# SP.net
KiCad netlist of a schematic drawn in EAGLE
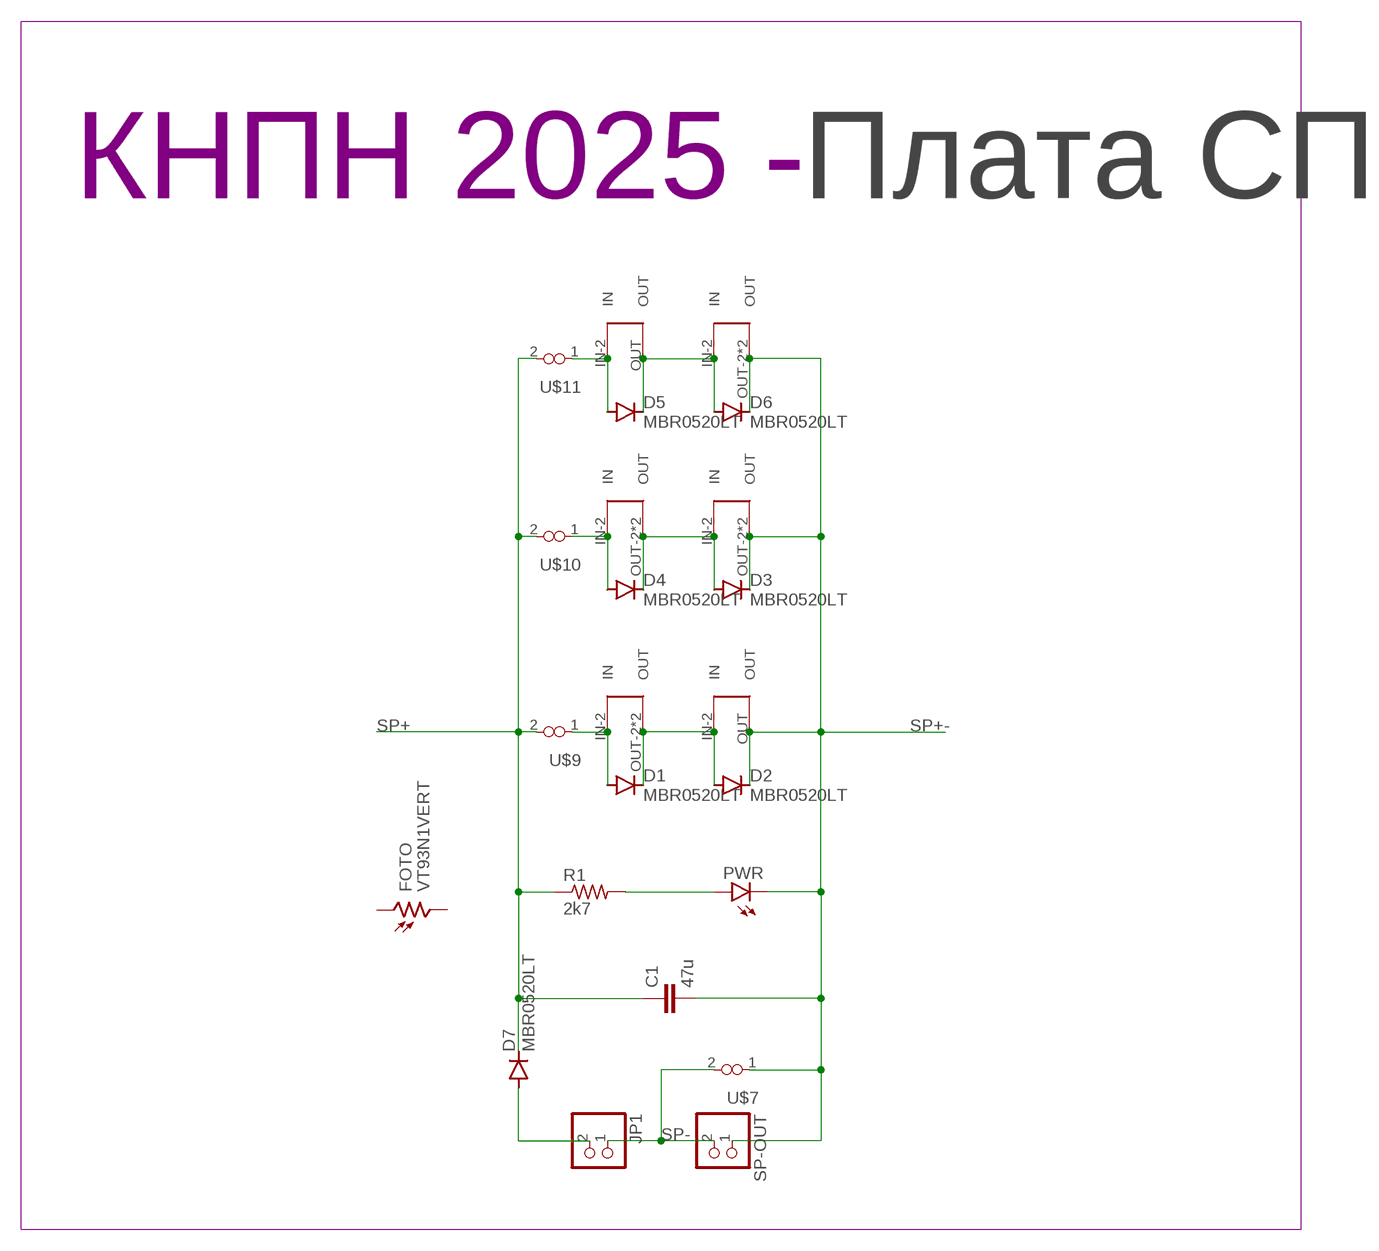
[diagram p0: schematic, sheet 1]

(export (version "E")
  (design (tool "Eeschema 10.0.6"))
  (components
    (comp (ref "C1")
      (value "47u")
      (footprint "eagle-import:C1210")
      (libsource (lib "eagle-import") (part "C-EUC1210"))
    )
    (comp (ref "D1")
      (value "MBR0520LT")
      (footprint "eagle-import:SOD123")
      (libsource (lib "eagle-import") (part "MBR0520LT"))
    )
    (comp (ref "D2")
      (value "MBR0520LT")
      (footprint "eagle-import:SOD123")
      (libsource (lib "eagle-import") (part "MBR0520LT"))
    )
    (comp (ref "D3")
      (value "MBR0520LT")
      (footprint "eagle-import:SOD123")
      (libsource (lib "eagle-import") (part "MBR0520LT"))
    )
    (comp (ref "D4")
      (value "MBR0520LT")
      (footprint "eagle-import:SOD123")
      (libsource (lib "eagle-import") (part "MBR0520LT"))
    )
    (comp (ref "D5")
      (value "MBR0520LT")
      (footprint "eagle-import:SOD123")
      (libsource (lib "eagle-import") (part "MBR0520LT"))
    )
    (comp (ref "D6")
      (value "MBR0520LT")
      (footprint "eagle-import:SOD123")
      (libsource (lib "eagle-import") (part "MBR0520LT"))
    )
    (comp (ref "D7")
      (value "MBR0520LT")
      (footprint "eagle-import:SOD123")
      (libsource (lib "eagle-import") (part "MBR0520LT"))
    )
    (comp (ref "FOTO")
      (value "VT93N1VERT")
      (footprint "eagle-import:VT93N1-VERT")
      (libsource (lib "eagle-import") (part "VT93N1VERT"))
    )
    (comp (ref "JP1")
      (value "PINHD-1X2")
      (footprint "eagle-import:1X02")
      (libsource (lib "eagle-import") (part "PINHD-1X2"))
    )
    (comp (ref "PWR")
      (value "LEDCHIP-LED0603")
      (footprint "eagle-import:CHIP-LED0603")
      (libsource (lib "eagle-import") (part "LEDCHIP-LED0603"))
    )
    (comp (ref "R1")
      (value "2k7")
      (footprint "eagle-import:R0603")
      (libsource (lib "eagle-import") (part "R-US_R0603"))
    )
    (comp (ref "SP-OUT")
      (value "PINHD-1X2")
      (footprint "eagle-import:1X02")
      (libsource (lib "eagle-import") (part "PINHD-1X2"))
    )
    (comp (ref "U$1")
      (value "SOLAR-2_INVERT0-2")
      (footprint "eagle-import:SOLAR_0-2_INVERT")
      (libsource (lib "eagle-import") (part "SOLAR-2_INVERT0-2"))
    )
    (comp (ref "U$2")
      (value "SOLAR-2_INVERT1-2")
      (footprint "eagle-import:SOLAR_1-2_INVERT")
      (libsource (lib "eagle-import") (part "SOLAR-2_INVERT1-2"))
    )
    (comp (ref "U$3")
      (value "SOLAR-2_INVERT0-2")
      (footprint "eagle-import:SOLAR_0-2_INVERT")
      (libsource (lib "eagle-import") (part "SOLAR-2_INVERT0-2"))
    )
    (comp (ref "U$4")
      (value "SOLAR-2_INVERT0-2")
      (footprint "eagle-import:SOLAR_0-2_INVERT")
      (libsource (lib "eagle-import") (part "SOLAR-2_INVERT0-2"))
    )
    (comp (ref "U$5")
      (value "Плата СП")
      (footprint "eagle-import:LOGO")
      (libsource (lib "eagle-import") (part "LOGOPCB-{dblquote}{dblquote}"))
    )
    (comp (ref "U$6")
      (value "SOLAR-2_INVERT1-2")
      (footprint "eagle-import:SOLAR_1-2_INVERT")
      (libsource (lib "eagle-import") (part "SOLAR-2_INVERT1-2"))
    )
    (comp (ref "U$7")
      (value "VIAS-CONNECT")
      (footprint "eagle-import:VIAS-CONNECT")
      (libsource (lib "eagle-import") (part "VIAS-CONNECT"))
    )
    (comp (ref "U$8")
      (value "SOLAR-2_INVERT0-2")
      (footprint "eagle-import:SOLAR_0-2_INVERT")
      (libsource (lib "eagle-import") (part "SOLAR-2_INVERT0-2"))
    )
    (comp (ref "U$9")
      (value "VIAS-CONNECT")
      (footprint "eagle-import:VIAS-CONNECT")
      (libsource (lib "eagle-import") (part "VIAS-CONNECT"))
    )
    (comp (ref "U$10")
      (value "VIAS-CONNECT")
      (footprint "eagle-import:VIAS-CONNECT")
      (libsource (lib "eagle-import") (part "VIAS-CONNECT"))
    )
    (comp (ref "U$11")
      (value "VIAS-CONNECT")
      (footprint "eagle-import:VIAS-CONNECT")
      (libsource (lib "eagle-import") (part "VIAS-CONNECT"))
    )
  )
  (nets
    (net (code "1") (name "/SP+") (class "Default")
      (node (ref "C1") (pin "1") (pinfunction "1_1") (pintype "passive"))
      (node (ref "D7") (pin "C") (pinfunction "C_C") (pintype "passive"))
      (node (ref "R1") (pin "1") (pinfunction "1_1") (pintype "passive"))
      (node (ref "U$10") (pin "2") (pinfunction "2_2") (pintype "passive"))
      (node (ref "U$11") (pin "2") (pinfunction "2_2") (pintype "passive"))
      (node (ref "U$9") (pin "2") (pinfunction "2_2") (pintype "passive"))
    )
    (net (code "2") (name "/SP+-") (class "Default")
      (node (ref "C1") (pin "2") (pinfunction "2_2") (pintype "passive"))
      (node (ref "D2") (pin "C") (pinfunction "C_C") (pintype "passive"))
      (node (ref "D3") (pin "C") (pinfunction "C_C") (pintype "passive"))
      (node (ref "D6") (pin "C") (pinfunction "C_C") (pintype "passive"))
      (node (ref "PWR") (pin "C") (pinfunction "C_C") (pintype "passive"))
      (node (ref "SP-OUT") (pin "1") (pinfunction "1_1") (pintype "passive"))
      (node (ref "U$2") (pin "OUT") (pinfunction "OUT_OUT") (pintype "bidirectional"))
      (node (ref "U$3") (pin "OUT-2") (pinfunction "OUT_OUT-2") (pintype "bidirectional"))
      (node (ref "U$3") (pin "OUT-21") (pinfunction "OUT_OUT-21") (pintype "bidirectional"))
      (node (ref "U$7") (pin "1") (pinfunction "1_1") (pintype "passive"))
      (node (ref "U$8") (pin "OUT-2") (pinfunction "OUT_OUT-2") (pintype "bidirectional"))
      (node (ref "U$8") (pin "OUT-21") (pinfunction "OUT_OUT-21") (pintype "bidirectional"))
    )
    (net (code "3") (name "/SP-") (class "Default")
      (node (ref "JP1") (pin "1") (pinfunction "1_1") (pintype "passive"))
      (node (ref "SP-OUT") (pin "2") (pinfunction "2_2") (pintype "passive"))
      (node (ref "U$7") (pin "2") (pinfunction "2_2") (pintype "passive"))
    )
    (net (code "4") (name "Net-(D7-PadA)") (class "Default")
      (node (ref "D7") (pin "A") (pinfunction "A_A") (pintype "passive"))
      (node (ref "JP1") (pin "2") (pinfunction "2_2") (pintype "passive"))
    )
    (net (code "5") (name "Net-(PWR-PadA)") (class "Default")
      (node (ref "PWR") (pin "A") (pinfunction "A_A") (pintype "passive"))
      (node (ref "R1") (pin "2") (pinfunction "2_2") (pintype "passive"))
    )
    (net (code "6") (name "Net-(U$1-IN)") (class "Default")
      (node (ref "D1") (pin "A") (pinfunction "A_A") (pintype "passive"))
      (node (ref "U$1") (pin "IN-2") (pinfunction "IN_IN-2") (pintype "bidirectional"))
      (node (ref "U$9") (pin "1") (pinfunction "1_1") (pintype "passive"))
    )
    (net (code "7") (name "Net-(U$2-IN)") (class "Default")
      (node (ref "D1") (pin "C") (pinfunction "C_C") (pintype "passive"))
      (node (ref "D2") (pin "A") (pinfunction "A_A") (pintype "passive"))
      (node (ref "U$1") (pin "OUT-2") (pinfunction "OUT_OUT-2") (pintype "bidirectional"))
      (node (ref "U$1") (pin "OUT-21") (pinfunction "OUT_OUT-21") (pintype "bidirectional"))
      (node (ref "U$2") (pin "IN-2") (pinfunction "IN_IN-2") (pintype "bidirectional"))
    )
    (net (code "8") (name "Net-(U$3-IN)") (class "Default")
      (node (ref "D3") (pin "A") (pinfunction "A_A") (pintype "passive"))
      (node (ref "D4") (pin "C") (pinfunction "C_C") (pintype "passive"))
      (node (ref "U$3") (pin "IN-2") (pinfunction "IN_IN-2") (pintype "bidirectional"))
      (node (ref "U$4") (pin "OUT-2") (pinfunction "OUT_OUT-2") (pintype "bidirectional"))
      (node (ref "U$4") (pin "OUT-21") (pinfunction "OUT_OUT-21") (pintype "bidirectional"))
    )
    (net (code "9") (name "Net-(U$4-IN)") (class "Default")
      (node (ref "D4") (pin "A") (pinfunction "A_A") (pintype "passive"))
      (node (ref "U$10") (pin "1") (pinfunction "1_1") (pintype "passive"))
      (node (ref "U$4") (pin "IN-2") (pinfunction "IN_IN-2") (pintype "bidirectional"))
    )
    (net (code "10") (name "Net-(U$6-IN)") (class "Default")
      (node (ref "D5") (pin "A") (pinfunction "A_A") (pintype "passive"))
      (node (ref "U$11") (pin "1") (pinfunction "1_1") (pintype "passive"))
      (node (ref "U$6") (pin "IN-2") (pinfunction "IN_IN-2") (pintype "bidirectional"))
    )
    (net (code "11") (name "Net-(U$8-IN)") (class "Default")
      (node (ref "D5") (pin "C") (pinfunction "C_C") (pintype "passive"))
      (node (ref "D6") (pin "A") (pinfunction "A_A") (pintype "passive"))
      (node (ref "U$6") (pin "OUT") (pinfunction "OUT_OUT") (pintype "bidirectional"))
      (node (ref "U$8") (pin "IN-2") (pinfunction "IN_IN-2") (pintype "bidirectional"))
    )
    (net (code "12") (name "unconnected-(FOTO-1-PadP$1)") (class "Default")
      (node (ref "FOTO") (pin "P$1") (pinfunction "1_P$1") (pintype "passive"))
    )
    (net (code "13") (name "unconnected-(FOTO-2-PadP$2)") (class "Default")
      (node (ref "FOTO") (pin "P$2") (pinfunction "2_P$2") (pintype "passive"))
    )
  )
)
